# Hydrated_Buffs.net
KiCad netlist of a schematic drawn in Altium Designer
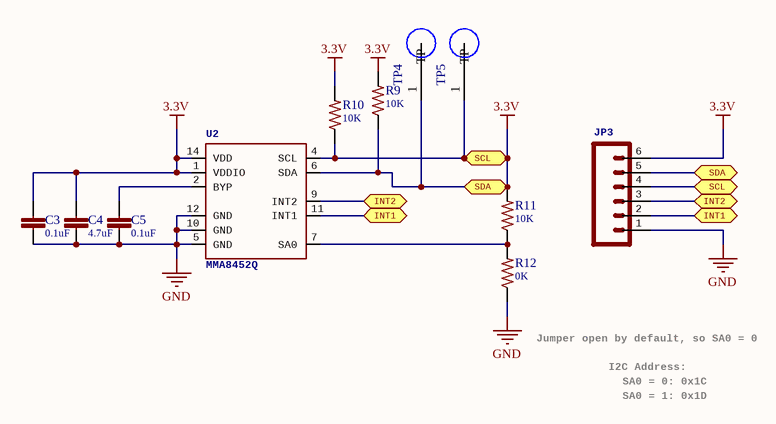
[diagram p0: Hydrated_Buffs.SchDoc]

(export (version "E")
  (design (tool "Eeschema 10.0.6"))
  (components
    (comp (ref "C3")
      (value "0.1uF")
      (fields (field (name "Comment") "Cap0.1uF"))
      (libsource (lib "Hydrated_Buffs") (part "Cap0.1uF"))
    )
    (comp (ref "C4")
      (value "4.7uF")
      (fields (field (name "Comment") "Cap4.7uF"))
      (libsource (lib "Hydrated_Buffs") (part "Cap4.7uF"))
    )
    (comp (ref "C5")
      (value "0.1uF")
      (fields (field (name "Comment") "Cap0.1uF"))
      (libsource (lib "Hydrated_Buffs") (part "Cap0.1uF"))
    )
    (comp (ref "JP3")
      (value "M06SIP")
      (footprint "1X06")
      (libsource (lib "SparkFun_MMA8452Q-Breakout") (part "M06SIP"))
    )
    (comp (ref "R9")
      (value "10K")
      (fields (field (name "Comment") "Res10K"))
      (libsource (lib "Hydrated_Buffs") (part "Res10K"))
    )
    (comp (ref "R10")
      (value "10K")
      (fields (field (name "Comment") "Res10K"))
      (libsource (lib "Hydrated_Buffs") (part "Res10K"))
    )
    (comp (ref "R11")
      (value "10K")
      (fields (field (name "Comment") "Res10K"))
      (libsource (lib "Hydrated_Buffs") (part "Res10K"))
    )
    (comp (ref "R12")
      (value "0K")
      (fields (field (name "Comment") "Res0K"))
      (libsource (lib "Hydrated_Buffs") (part "Res0K"))
    )
    (comp (ref "TP4")
      (value "5019")
      (footprint "*TP380X203")
      (description "Phosphor Bronze Contact Miniature Silver Plated Surface Mount Test Points")
      (fields (field (name "MF") "Keystone Electronics"))
      (libsource (lib "5019") (part "5019"))
    )
    (comp (ref "TP5")
      (value "5019")
      (footprint "*TP380X203")
      (description "Phosphor Bronze Contact Miniature Silver Plated Surface Mount Test Points")
      (fields (field (name "MF") "Keystone Electronics"))
      (libsource (lib "5019") (part "5019"))
    )
    (comp (ref "U2")
      (value "MMA8452Q")
      (footprint "QFN-16_0.5MM")
      (libsource (lib "Hydrated_Buffs") (part "MMA8452Q"))
    )
  )
  (nets
    (net (code "1") (name "/INT1") (class "Default")
      (node (ref "JP3") (pin "2") (pinfunction "2_2") (pintype "passive"))
      (node (ref "U2") (pin "11") (pinfunction "INT1_11") (pintype "passive"))
    )
    (net (code "2") (name "/INT2") (class "Default")
      (node (ref "JP3") (pin "3") (pinfunction "3_3") (pintype "passive"))
      (node (ref "U2") (pin "9") (pinfunction "INT2_9") (pintype "passive"))
    )
    (net (code "3") (name "3.3V") (class "Default")
      (node (ref "C3") (pin "1") (pinfunction "1_1") (pintype "passive"))
      (node (ref "C4") (pin "1") (pinfunction "1_1") (pintype "passive"))
      (node (ref "JP3") (pin "4") (pinfunction "4_4") (pintype "passive"))
      (node (ref "JP3") (pin "5") (pinfunction "5_5") (pintype "passive"))
      (node (ref "JP3") (pin "6") (pinfunction "6_6") (pintype "passive"))
      (node (ref "R10") (pin "1") (pinfunction "1_1") (pintype "passive"))
      (node (ref "R10") (pin "2") (pinfunction "2_2") (pintype "passive"))
      (node (ref "R11") (pin "2") (pinfunction "2_2") (pintype "passive"))
      (node (ref "R9") (pin "1") (pinfunction "1_1") (pintype "passive"))
      (node (ref "R9") (pin "2") (pinfunction "2_2") (pintype "passive"))
      (node (ref "TP4") (pin "1") (pinfunction "TP_1") (pintype "passive"))
      (node (ref "TP5") (pin "1") (pinfunction "TP_1") (pintype "passive"))
      (node (ref "U2") (pin "1") (pinfunction "VDDIO_1") (pintype "passive"))
      (node (ref "U2") (pin "14") (pinfunction "VDD_14") (pintype "passive"))
      (node (ref "U2") (pin "4") (pinfunction "SCL_4") (pintype "passive"))
      (node (ref "U2") (pin "6") (pinfunction "SDA_6") (pintype "passive"))
    )
    (net (code "4") (name "GND") (class "Default")
      (node (ref "C3") (pin "2") (pinfunction "2_2") (pintype "passive"))
      (node (ref "C4") (pin "2") (pinfunction "2_2") (pintype "passive"))
      (node (ref "C5") (pin "2") (pinfunction "2_2") (pintype "passive"))
      (node (ref "JP3") (pin "1") (pinfunction "1_1") (pintype "passive"))
      (node (ref "R12") (pin "1") (pinfunction "1_1") (pintype "passive"))
      (node (ref "U2") (pin "10") (pinfunction "GND_10") (pintype "passive"))
      (node (ref "U2") (pin "12") (pinfunction "GND_12") (pintype "passive"))
      (node (ref "U2") (pin "5") (pinfunction "GND_5") (pintype "passive"))
    )
    (net (code "5") (name "Net-(U2-BYP)") (class "Default")
      (node (ref "C5") (pin "1") (pinfunction "1_1") (pintype "passive"))
      (node (ref "U2") (pin "2") (pinfunction "BYP_2") (pintype "passive"))
    )
    (net (code "6") (name "Net-(U2-SA0)") (class "Default")
      (node (ref "R11") (pin "1") (pinfunction "1_1") (pintype "passive"))
      (node (ref "R12") (pin "2") (pinfunction "2_2") (pintype "passive"))
      (node (ref "U2") (pin "7") (pinfunction "SA0_7") (pintype "passive"))
    )
  )
)
